# TLE5012.net
KiCad netlist of a schematic drawn in Altium Designer
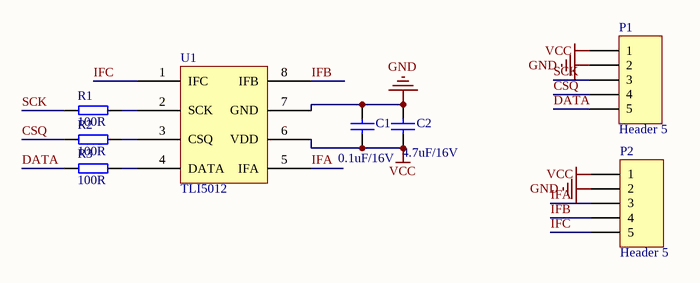
[diagram p0: TLE5012.SchDoc]

(export (version "E")
  (design (tool "Eeschema 10.0.6"))
  (components
    (comp (ref "C1")
      (value "0.1uF/16V")
      (footprint "zijianku:C0603")
      (libsource (lib "zijianku") (part "cap"))
    )
    (comp (ref "C2")
      (value "4.7uF/16V")
      (footprint "zijianku:C0603")
      (libsource (lib "zijianku") (part "cap"))
    )
    (comp (ref "P1")
      (value "Header 5")
      (footprint "molex 53261-0571")
      (description "Header, 5-Pin")
      (fields (field (name "PUBLISHER") "Altium Limited"))
      (libsource (lib "Common Headers") (part "Header 5"))
    )
    (comp (ref "P2")
      (value "Header 5")
      (footprint "molex 53261-0571")
      (description "Header, 5-Pin")
      (fields (field (name "PUBLISHER") "Altium Limited"))
      (libsource (lib "Common Headers") (part "Header 5"))
    )
    (comp (ref "R1") (value "100R") (footprint "R0603") (libsource (lib "zijianku") (part "Resistance")))
    (comp (ref "R2") (value "100R") (footprint "R0603") (libsource (lib "zijianku") (part "Resistance")))
    (comp (ref "R3") (value "100R") (footprint "R0603") (libsource (lib "zijianku") (part "Resistance")))
    (comp (ref "U1") (value "TLI5012") (footprint "SOIC-8") (libsource (lib "zijianku") (part "TLE5012")))
  )
  (nets
    (net (code "1") (name "/CSQ") (class "Default")
      (node (ref "P1") (pin "4") (pinfunction "4_4") (pintype "passive"))
      (node (ref "R2") (pin "1") (pintype "passive"))
    )
    (net (code "2") (name "/DATA") (class "Default")
      (node (ref "P1") (pin "5") (pinfunction "5_5") (pintype "passive"))
      (node (ref "R3") (pin "1") (pintype "passive"))
    )
    (net (code "3") (name "/IFA") (class "Default")
      (node (ref "P2") (pin "3") (pinfunction "3_3") (pintype "passive"))
      (node (ref "U1") (pin "5") (pinfunction "IFA_5") (pintype "passive"))
    )
    (net (code "4") (name "/IFB") (class "Default")
      (node (ref "P2") (pin "4") (pinfunction "4_4") (pintype "passive"))
      (node (ref "U1") (pin "8") (pinfunction "IFB_8") (pintype "passive"))
    )
    (net (code "5") (name "/IFC") (class "Default")
      (node (ref "P2") (pin "5") (pinfunction "5_5") (pintype "passive"))
      (node (ref "U1") (pin "1") (pinfunction "IFC_1") (pintype "passive"))
    )
    (net (code "6") (name "/SCK") (class "Default")
      (node (ref "P1") (pin "3") (pinfunction "3_3") (pintype "passive"))
      (node (ref "R1") (pin "1") (pintype "passive"))
    )
    (net (code "7") (name "GND") (class "Default")
      (node (ref "C1") (pin "2") (pinfunction "1_2") (pintype "passive"))
      (node (ref "C2") (pin "2") (pinfunction "1_2") (pintype "passive"))
      (node (ref "P1") (pin "2") (pinfunction "2_2") (pintype "passive"))
      (node (ref "P2") (pin "2") (pinfunction "2_2") (pintype "passive"))
      (node (ref "U1") (pin "7") (pinfunction "GND_7") (pintype "passive"))
    )
    (net (code "8") (name "Net-(U1-CSQ)") (class "Default")
      (node (ref "R2") (pin "2") (pintype "passive"))
      (node (ref "U1") (pin "3") (pinfunction "CSQ_3") (pintype "passive"))
    )
    (net (code "9") (name "Net-(U1-DATA)") (class "Default")
      (node (ref "R3") (pin "2") (pintype "passive"))
      (node (ref "U1") (pin "4") (pinfunction "DATA_4") (pintype "passive"))
    )
    (net (code "10") (name "Net-(U1-SCK)") (class "Default")
      (node (ref "R1") (pin "2") (pintype "passive"))
      (node (ref "U1") (pin "2") (pinfunction "SCK_2") (pintype "passive"))
    )
    (net (code "11") (name "VCC") (class "Default")
      (node (ref "C1") (pin "1") (pinfunction "0_1") (pintype "passive"))
      (node (ref "C2") (pin "1") (pinfunction "0_1") (pintype "passive"))
      (node (ref "P1") (pin "1") (pinfunction "1_1") (pintype "passive"))
      (node (ref "P2") (pin "1") (pinfunction "1_1") (pintype "passive"))
      (node (ref "U1") (pin "6") (pinfunction "VDD_6") (pintype "passive"))
    )
  )
)
